# MB1297_NFC_SAFE.net
KiCad netlist of a schematic drawn in Altium Designer
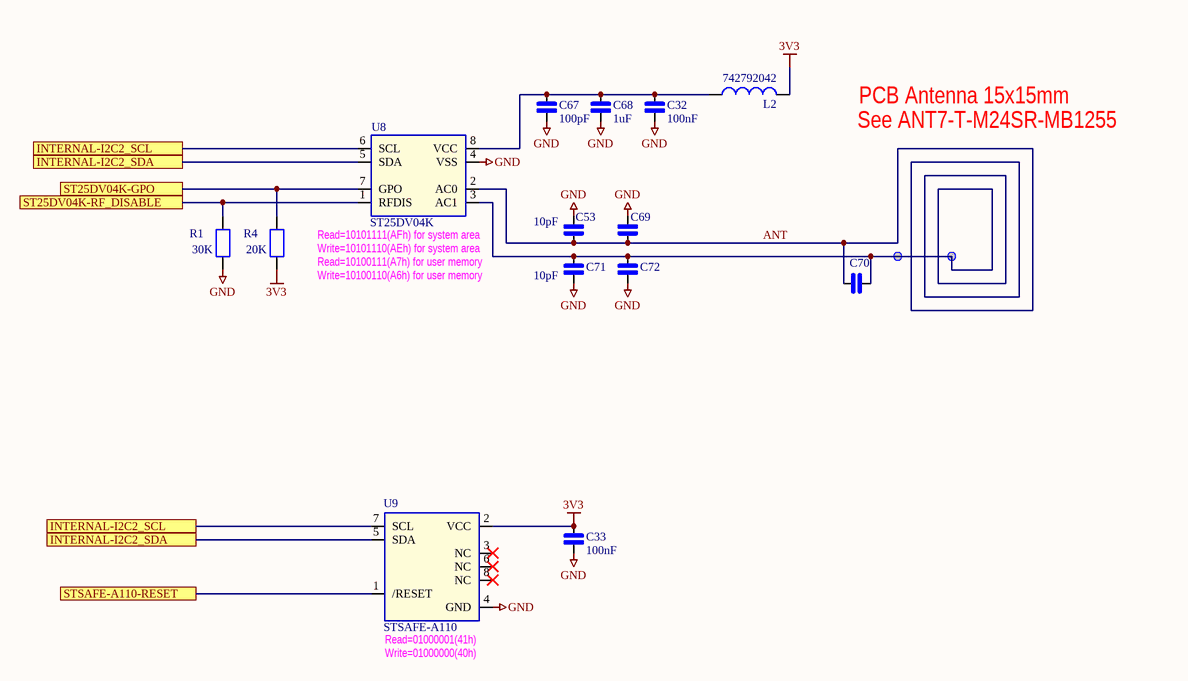
[diagram p0: MB1297_NFC_SAFE.SchDoc]

(export (version "E")
  (design (tool "Eeschema 10.0.6"))
  (components
    (comp (ref "C32")
      (value "100nF")
      (footprint "0402")
      (description "Capacitor_not polarized")
      (libsource (lib "ST_Lib3D") (part "CAP_NPOL"))
    )
    (comp (ref "C33")
      (value "100nF")
      (footprint "0402")
      (description "Capacitor_not polarized")
      (libsource (lib "ST_Lib3D") (part "CAP_NPOL"))
    )
    (comp (ref "C53")
      (value "10pF")
      (footprint "0402")
      (description "Capacitor_not polarized")
      (libsource (lib "ST_Lib3D") (part "CAP_NPOL"))
    )
    (comp (ref "C67")
      (value "100pF")
      (footprint "0402")
      (description "Capacitor_not polarized")
      (libsource (lib "ST_Lib3D") (part "CAP_NPOL"))
    )
    (comp (ref "C68")
      (value "1uF")
      (footprint "0402")
      (description "Capacitor_not polarized")
      (libsource (lib "ST_Lib3D") (part "CAP_NPOL"))
    )
    (comp (ref "C69")
      (value "~")
      (footprint "0402")
      (description "Capacitor_not polarized")
      (libsource (lib "ST_Lib3D") (part "CAP_NPOL"))
    )
    (comp (ref "C70")
      (value "~")
      (footprint "0402")
      (description "Capacitor_not polarized")
      (libsource (lib "ST_Lib3D") (part "CAP_NPOL"))
    )
    (comp (ref "C71")
      (value "10pF")
      (footprint "0402")
      (description "Capacitor_not polarized")
      (libsource (lib "ST_Lib3D") (part "CAP_NPOL"))
    )
    (comp (ref "C72")
      (value "~")
      (footprint "0402")
      (description "Capacitor_not polarized")
      (libsource (lib "ST_Lib3D") (part "CAP_NPOL"))
    )
    (comp (ref "L2")
      (value "742792042")
      (footprint "0603L")
      (description "Inductor")
      (fields (field (name "PUBLISHER") "Altium Limited"))
      (libsource (lib "Miscellaneous Devices") (part "Inductor"))
    )
    (comp (ref "R1")
      (value "30K")
      (footprint "0402")
      (description "Resistor")
      (libsource (lib "ST_Lib3D") (part "RES"))
    )
    (comp (ref "R4")
      (value "20K")
      (footprint "0402")
      (description "Resistor")
      (libsource (lib "ST_Lib3D") (part "RES"))
    )
    (comp (ref "U8")
      (value "ST25DV04K")
      (footprint "SOP8")
      (description "ST25DV04K 64K_EEPROM NFC/RFID")
      (libsource (lib "ST_Lib3D") (part "M24SR64-Y"))
    )
    (comp (ref "U9")
      (value "STSAFE-A110")
      (footprint "SOP8")
      (description "STSAFE-A100")
      (libsource (lib "ST_Lib3D") (part "STSAFE-A100"))
    )
  )
  (nets
    (net (code "1") (name "/ANT") (class "Default")
      (node (ref "C53") (pin "1") (pinfunction "1_1") (pintype "passive"))
      (node (ref "C69") (pin "1") (pinfunction "1_1") (pintype "passive"))
      (node (ref "C70") (pin "1") (pinfunction "1_1") (pintype "passive"))
      (node (ref "C70") (pin "2") (pinfunction "2_2") (pintype "passive"))
      (node (ref "C71") (pin "1") (pinfunction "1_1") (pintype "passive"))
      (node (ref "C72") (pin "1") (pinfunction "1_1") (pintype "passive"))
      (node (ref "U8") (pin "2") (pinfunction "AC0_2") (pintype "passive"))
      (node (ref "U8") (pin "3") (pinfunction "AC1_3") (pintype "passive"))
    )
    (net (code "2") (name "/INTERNAL-I2C2_SCL") (class "Default")
      (node (ref "U8") (pin "6") (pinfunction "SCL_6") (pintype "passive"))
      (node (ref "U9") (pin "7") (pinfunction "SCL_7") (pintype "passive"))
    )
    (net (code "3") (name "/INTERNAL-I2C2_SDA") (class "Default")
      (node (ref "U8") (pin "5") (pinfunction "SDA_5") (pintype "passive"))
      (node (ref "U9") (pin "5") (pinfunction "SDA_5") (pintype "passive"))
    )
    (net (code "4") (name "/ST25DV04K-GPO") (class "Default")
      (node (ref "R4") (pin "2") (pinfunction "2_2") (pintype "passive"))
      (node (ref "U8") (pin "7") (pinfunction "GPO_7") (pintype "passive"))
    )
    (net (code "5") (name "/ST25DV04K-RF_DISABLE") (class "Default")
      (node (ref "R1") (pin "2") (pinfunction "2_2") (pintype "passive"))
      (node (ref "U8") (pin "1") (pinfunction "RFDIS_1") (pintype "passive"))
    )
    (net (code "6") (name "/STSAFE-A110-RESET") (class "Default")
      (node (ref "U9") (pin "1") (pinfunction "/RESET_1") (pintype "passive"))
    )
    (net (code "7") (name "3V3") (class "Default")
      (node (ref "C33") (pin "1") (pinfunction "1_1") (pintype "passive"))
      (node (ref "L2") (pin "2") (pinfunction "2_2") (pintype "passive"))
      (node (ref "R4") (pin "1") (pinfunction "1_1") (pintype "passive"))
      (node (ref "U9") (pin "2") (pinfunction "VCC_2") (pintype "passive"))
    )
    (net (code "8") (name "GND") (class "Default")
      (node (ref "C32") (pin "2") (pinfunction "2_2") (pintype "passive"))
      (node (ref "C33") (pin "2") (pinfunction "2_2") (pintype "passive"))
      (node (ref "C53") (pin "2") (pinfunction "2_2") (pintype "passive"))
      (node (ref "C67") (pin "2") (pinfunction "2_2") (pintype "passive"))
      (node (ref "C68") (pin "2") (pinfunction "2_2") (pintype "passive"))
      (node (ref "C69") (pin "2") (pinfunction "2_2") (pintype "passive"))
      (node (ref "C71") (pin "2") (pinfunction "2_2") (pintype "passive"))
      (node (ref "C72") (pin "2") (pinfunction "2_2") (pintype "passive"))
      (node (ref "R1") (pin "1") (pinfunction "1_1") (pintype "passive"))
      (node (ref "U8") (pin "4") (pinfunction "VSS_4") (pintype "passive"))
      (node (ref "U9") (pin "4") (pinfunction "GND_4") (pintype "passive"))
    )
    (net (code "9") (name "Net-(U8-VCC)") (class "Default")
      (node (ref "C32") (pin "1") (pinfunction "1_1") (pintype "passive"))
      (node (ref "C67") (pin "1") (pinfunction "1_1") (pintype "passive"))
      (node (ref "C68") (pin "1") (pinfunction "1_1") (pintype "passive"))
      (node (ref "L2") (pin "1") (pinfunction "1_1") (pintype "passive"))
      (node (ref "U8") (pin "8") (pinfunction "VCC_8") (pintype "passive"))
    )
    (net (code "10") (name "unconnected-(U9-NC-Pad3)") (class "Default")
      (node (ref "U9") (pin "3") (pinfunction "NC_3") (pintype "passive+no_connect"))
    )
    (net (code "11") (name "unconnected-(U9-NC-Pad6)") (class "Default")
      (node (ref "U9") (pin "6") (pinfunction "NC_6") (pintype "passive+no_connect"))
    )
    (net (code "12") (name "unconnected-(U9-NC-Pad8)") (class "Default")
      (node (ref "U9") (pin "8") (pinfunction "NC_8") (pintype "passive+no_connect"))
    )
  )
)
